# bbr18_thrower_board.net
KiCad netlist of a schematic drawn in Altium Designer
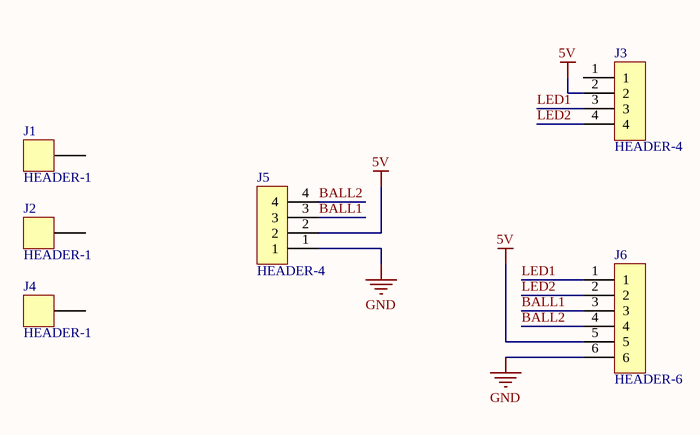
[diagram p0: bbr18_thrower_board.SchDoc]

(export (version "E")
  (design (tool "Eeschema 10.0.6"))
  (components
    (comp (ref "J1")
      (value "HEADER-1")
      (footprint "2MM-BULLET-PLUG-VIA")
      (libsource (lib "connectors") (part "HEADER-1"))
    )
    (comp (ref "J2")
      (value "HEADER-1")
      (footprint "2MM-BULLET-PLUG-VIA")
      (libsource (lib "connectors") (part "HEADER-1"))
    )
    (comp (ref "J3")
      (value "HEADER-4")
      (footprint "MICRO-MATCH-FOB-SIDE-04")
      (libsource (lib "") (part "HEADER-4_1"))
    )
    (comp (ref "J4")
      (value "HEADER-1")
      (footprint "2MM-BULLET-PLUG-VIA")
      (libsource (lib "connectors") (part "HEADER-1"))
    )
    (comp (ref "J5")
      (value "HEADER-4")
      (footprint "MICRO-MATCH-MOB-04")
      (libsource (lib "connectors_micromatch") (part "HEADER-4"))
    )
    (comp (ref "J6")
      (value "HEADER-6")
      (footprint "MICRO-MATCH-FOB-SIDE-06")
      (libsource (lib "connectors_micromatch") (part "HEADER-6"))
    )
  )
  (nets
    (net (code "1") (name "/BALL1") (class "Default")
      (node (ref "J5") (pin "3") (pinfunction "3_3") (pintype "passive"))
      (node (ref "J6") (pin "3") (pinfunction "3_3") (pintype "passive"))
    )
    (net (code "2") (name "/BALL2") (class "Default")
      (node (ref "J5") (pin "4") (pinfunction "4_4") (pintype "passive"))
      (node (ref "J6") (pin "4") (pinfunction "4_4") (pintype "passive"))
    )
    (net (code "3") (name "/LED1") (class "Default")
      (node (ref "J3") (pin "3") (pinfunction "3_3") (pintype "passive"))
      (node (ref "J6") (pin "1") (pinfunction "1_1") (pintype "passive"))
    )
    (net (code "4") (name "/LED2") (class "Default")
      (node (ref "J3") (pin "4") (pinfunction "4_4") (pintype "passive"))
      (node (ref "J6") (pin "2") (pinfunction "2_2") (pintype "passive"))
    )
    (net (code "5") (name "5V") (class "Default")
      (node (ref "J3") (pin "2") (pinfunction "2_2") (pintype "passive"))
      (node (ref "J5") (pin "2") (pinfunction "2_2") (pintype "passive"))
      (node (ref "J6") (pin "5") (pinfunction "5_5") (pintype "passive"))
    )
    (net (code "6") (name "GND") (class "Default")
      (node (ref "J5") (pin "1") (pinfunction "1_1") (pintype "passive"))
      (node (ref "J6") (pin "6") (pinfunction "6_6") (pintype "passive"))
    )
    (net (code "7") (name "unconnected-(J1-Pad1)") (class "Default")
      (node (ref "J1") (pin "1") (pinfunction "1_1") (pintype "passive"))
    )
    (net (code "8") (name "unconnected-(J2-Pad1)") (class "Default")
      (node (ref "J2") (pin "1") (pinfunction "1_1") (pintype "passive"))
    )
    (net (code "9") (name "unconnected-(J3-Pad1)") (class "Default")
      (node (ref "J3") (pin "1") (pinfunction "1_1") (pintype "passive"))
    )
    (net (code "10") (name "unconnected-(J4-Pad1)") (class "Default")
      (node (ref "J4") (pin "1") (pinfunction "1_1") (pintype "passive"))
    )
  )
)
